# akim_sensorleri.net
KiCad netlist of a schematic drawn in EAGLE
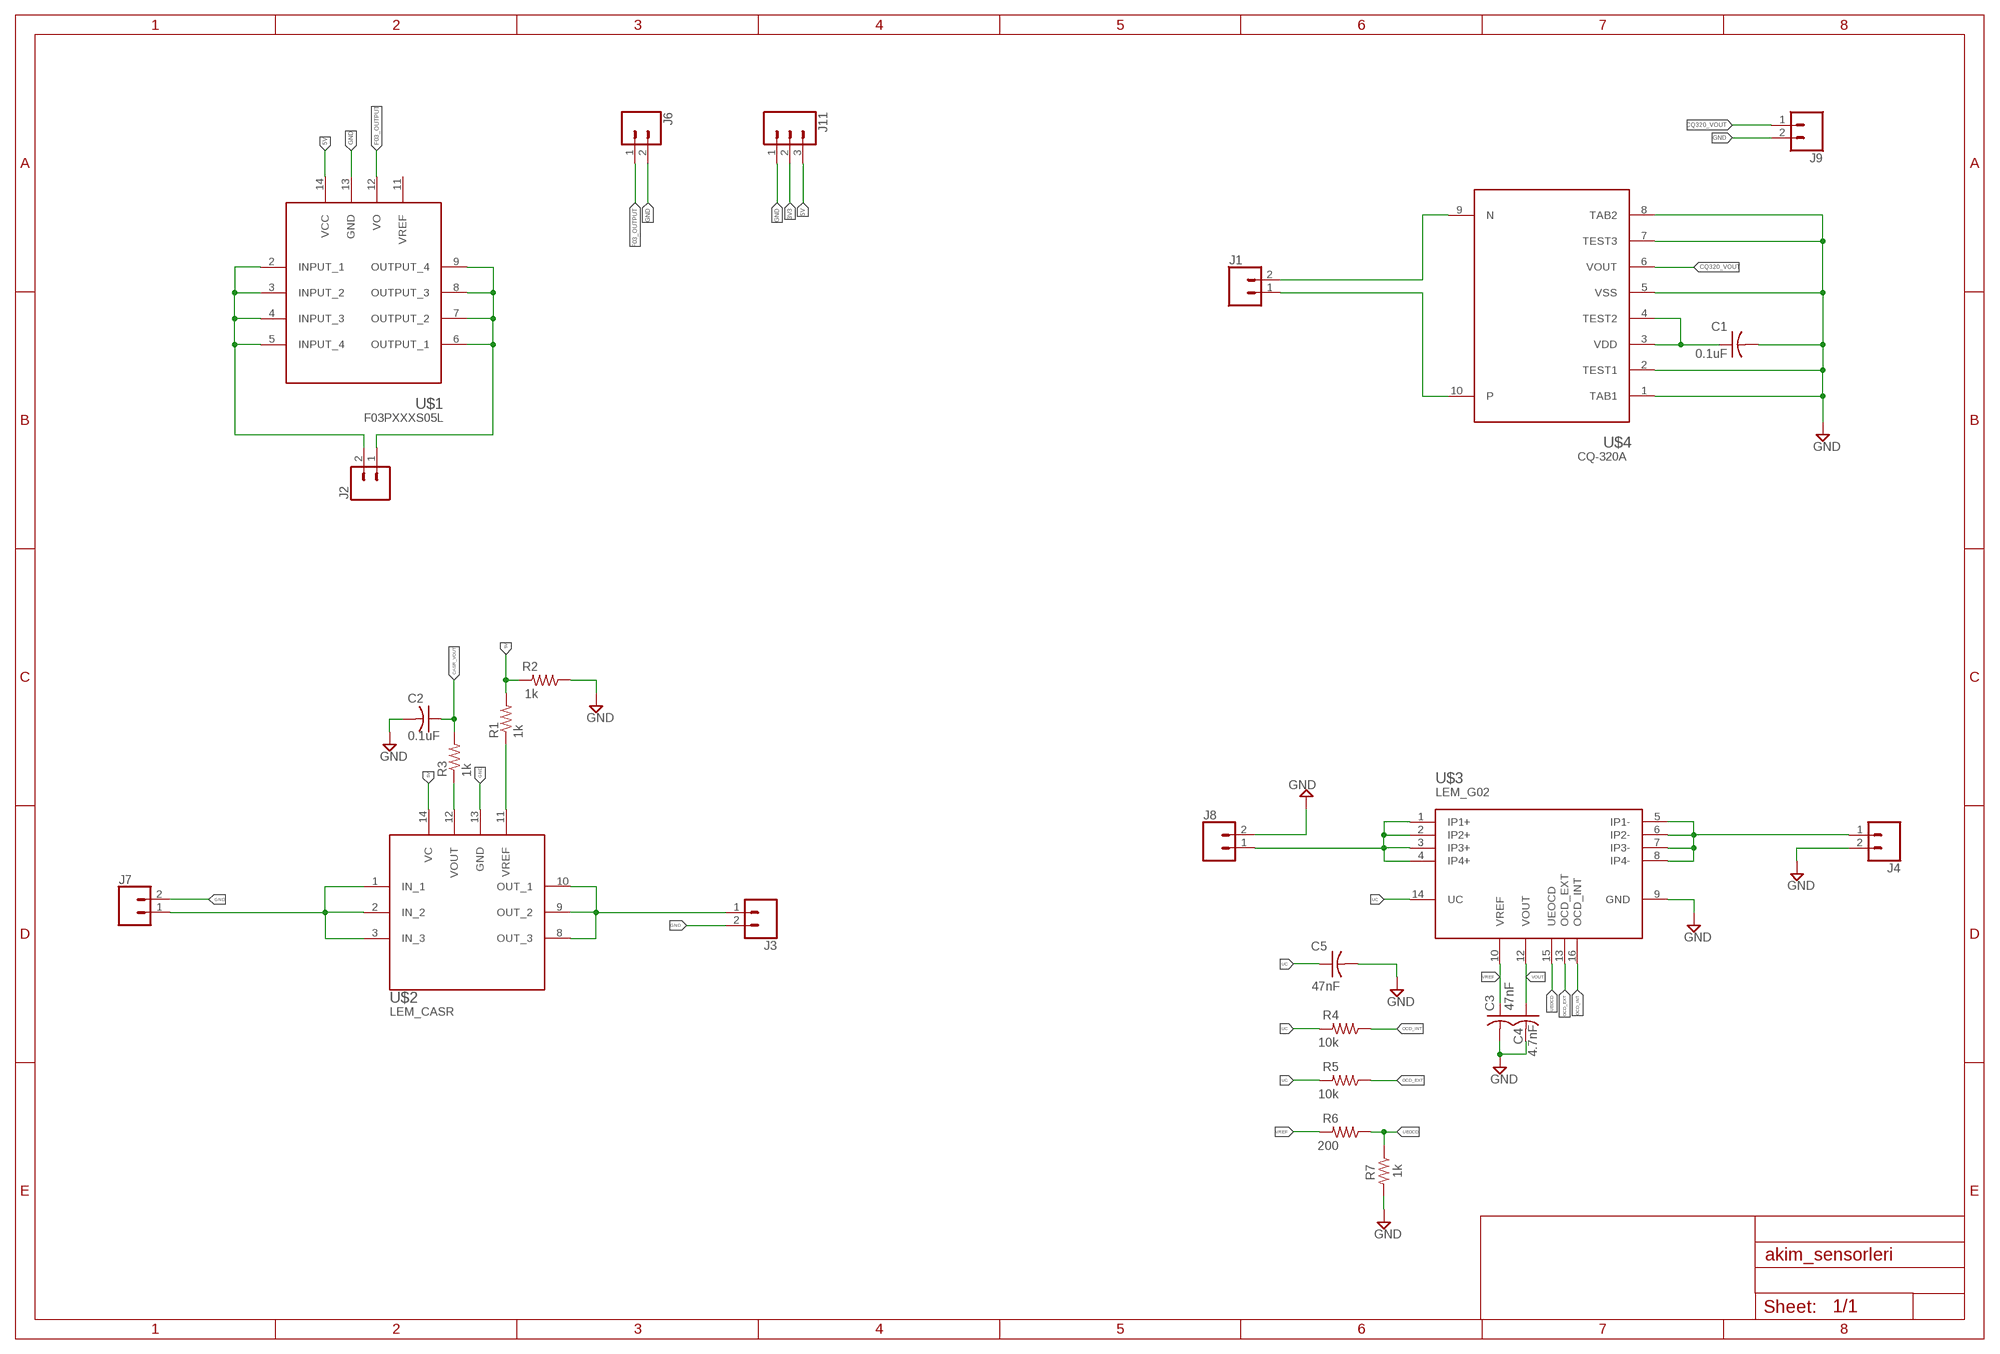
[diagram p0: schematic, sheet 1]

(export (version "E")
  (design (tool "Eeschema 10.0.6"))
  (components
    (comp (ref "C1")
      (value "0.1uF")
      (footprint "eagle-import:C1206")
      (libsource (lib "eagle-import") (part "C-USC1206"))
    )
    (comp (ref "C2")
      (value "0.1uF")
      (footprint "eagle-import:C1206")
      (libsource (lib "eagle-import") (part "C-USC1206"))
    )
    (comp (ref "C3")
      (value "47nF")
      (footprint "eagle-import:C1206")
      (libsource (lib "eagle-import") (part "C-USC1206"))
    )
    (comp (ref "C4")
      (value "4.7nF")
      (footprint "eagle-import:C1206")
      (libsource (lib "eagle-import") (part "C-USC1206"))
    )
    (comp (ref "C5")
      (value "47nF")
      (footprint "eagle-import:C1206")
      (libsource (lib "eagle-import") (part "C-USC1206"))
    )
    (comp (ref "J1")
      (value "CONN_025MM")
      (footprint "eagle-import:SCREWTERMINAL-5MM-2")
      (libsource (lib "eagle-import") (part "CONN_025MM"))
    )
    (comp (ref "J2")
      (value "CONN_025MM")
      (footprint "eagle-import:SCREWTERMINAL-5MM-2")
      (libsource (lib "eagle-import") (part "CONN_025MM"))
    )
    (comp (ref "J3")
      (value "CONN_025MM")
      (footprint "eagle-import:SCREWTERMINAL-5MM-2")
      (libsource (lib "eagle-import") (part "CONN_025MM"))
    )
    (comp (ref "J4")
      (value "CONN_025MM")
      (footprint "eagle-import:SCREWTERMINAL-5MM-2")
      (libsource (lib "eagle-import") (part "CONN_025MM"))
    )
    (comp (ref "J6")
      (value "CONN_025MM")
      (footprint "eagle-import:SCREWTERMINAL-5MM-2")
      (libsource (lib "eagle-import") (part "CONN_025MM"))
    )
    (comp (ref "J7")
      (value "CONN_025MM")
      (footprint "eagle-import:SCREWTERMINAL-5MM-2")
      (libsource (lib "eagle-import") (part "CONN_025MM"))
    )
    (comp (ref "J8")
      (value "CONN_025MM")
      (footprint "eagle-import:SCREWTERMINAL-5MM-2")
      (libsource (lib "eagle-import") (part "CONN_025MM"))
    )
    (comp (ref "J9")
      (value "CONN_025MM")
      (footprint "eagle-import:SCREWTERMINAL-5MM-2")
      (libsource (lib "eagle-import") (part "CONN_025MM"))
    )
    (comp (ref "J11")
      (value "CONN_03-SCREW-5MM")
      (footprint "eagle-import:SCREWTERMINAL-5MM-3")
      (libsource (lib "eagle-import") (part "CONN_03-SCREW-5MM"))
    )
    (comp (ref "R1")
      (value "1k")
      (footprint "eagle-import:M1206")
      (libsource (lib "eagle-import") (part "R-US_M1206"))
    )
    (comp (ref "R2")
      (value "1k")
      (footprint "eagle-import:M1206")
      (libsource (lib "eagle-import") (part "R-US_M1206"))
    )
    (comp (ref "R3")
      (value "1k")
      (footprint "eagle-import:M1206")
      (libsource (lib "eagle-import") (part "R-US_M1206"))
    )
    (comp (ref "R4")
      (value "10k")
      (footprint "eagle-import:M1206")
      (libsource (lib "eagle-import") (part "R-US_M1206"))
    )
    (comp (ref "R5")
      (value "10k")
      (footprint "eagle-import:M1206")
      (libsource (lib "eagle-import") (part "R-US_M1206"))
    )
    (comp (ref "R6")
      (value "200")
      (footprint "eagle-import:M1206")
      (libsource (lib "eagle-import") (part "R-US_M1206"))
    )
    (comp (ref "R7")
      (value "1k")
      (footprint "eagle-import:M1206")
      (libsource (lib "eagle-import") (part "R-US_M1206"))
    )
    (comp (ref "U$1")
      (value "F03PXXXS05L")
      (footprint "eagle-import:F03PXXXS05L")
      (libsource (lib "eagle-import") (part "F03PXXXS05L"))
    )
    (comp (ref "U$2")
      (value "LEM_CASR")
      (footprint "eagle-import:LEM")
      (libsource (lib "eagle-import") (part "LEM_CASR"))
    )
    (comp (ref "U$3")
      (value "LEM_G02")
      (footprint "eagle-import:LEM_G02")
      (libsource (lib "eagle-import") (part "LEM_G02"))
    )
    (comp (ref "U$4")
      (value "CQ-320A")
      (footprint "eagle-import:CQ-320A")
      (libsource (lib "eagle-import") (part "CQ-320A"))
    )
  )
  (nets
    (net (code "1") (name "3V3") (class "Default")
      (node (ref "J11") (pin "2") (pinfunction "2_2") (pintype "passive"))
    )
    (net (code "2") (name "5V") (class "Default")
      (node (ref "J11") (pin "3") (pinfunction "3_3") (pintype "passive"))
      (node (ref "R1") (pin "2") (pinfunction "2_2") (pintype "passive"))
      (node (ref "R2") (pin "2") (pinfunction "2_2") (pintype "passive"))
      (node (ref "U$1") (pin "14") (pinfunction "VCC_14") (pintype "bidirectional"))
      (node (ref "U$2") (pin "14") (pinfunction "VC_14") (pintype "bidirectional"))
    )
    (net (code "3") (name "CASR_VOUT") (class "Default")
      (node (ref "C2") (pin "1") (pinfunction "1_1") (pintype "passive"))
      (node (ref "R3") (pin "2") (pinfunction "2_2") (pintype "passive"))
    )
    (net (code "4") (name "CQ320_VOUT") (class "Default")
      (node (ref "J9") (pin "1") (pinfunction "1_1") (pintype "passive"))
      (node (ref "U$4") (pin "6") (pinfunction "VOUT_6") (pintype "bidirectional"))
    )
    (net (code "5") (name "F03_OUTPUT") (class "Default")
      (node (ref "J6") (pin "1") (pinfunction "1_1") (pintype "passive"))
      (node (ref "U$1") (pin "12") (pinfunction "VO_12") (pintype "bidirectional"))
    )
    (net (code "6") (name "GND") (class "Default")
      (node (ref "C1") (pin "2") (pinfunction "2_2") (pintype "passive"))
      (node (ref "C2") (pin "2") (pinfunction "2_2") (pintype "passive"))
      (node (ref "C3") (pin "2") (pinfunction "2_2") (pintype "passive"))
      (node (ref "C4") (pin "2") (pinfunction "2_2") (pintype "passive"))
      (node (ref "C5") (pin "2") (pinfunction "2_2") (pintype "passive"))
      (node (ref "J11") (pin "1") (pinfunction "1_1") (pintype "passive"))
      (node (ref "J3") (pin "2") (pinfunction "2_2") (pintype "passive"))
      (node (ref "J4") (pin "2") (pinfunction "2_2") (pintype "passive"))
      (node (ref "J6") (pin "2") (pinfunction "2_2") (pintype "passive"))
      (node (ref "J7") (pin "2") (pinfunction "2_2") (pintype "passive"))
      (node (ref "J8") (pin "2") (pinfunction "2_2") (pintype "passive"))
      (node (ref "J9") (pin "2") (pinfunction "2_2") (pintype "passive"))
      (node (ref "R2") (pin "1") (pinfunction "1_1") (pintype "passive"))
      (node (ref "R7") (pin "2") (pinfunction "2_2") (pintype "passive"))
      (node (ref "U$1") (pin "13") (pinfunction "GND_13") (pintype "bidirectional"))
      (node (ref "U$2") (pin "13") (pinfunction "GND_13") (pintype "bidirectional"))
      (node (ref "U$3") (pin "9") (pinfunction "GND_9") (pintype "bidirectional"))
      (node (ref "U$4") (pin "1") (pinfunction "TAB1_1") (pintype "bidirectional"))
      (node (ref "U$4") (pin "2") (pinfunction "TEST1_2") (pintype "bidirectional"))
      (node (ref "U$4") (pin "5") (pinfunction "VSS_5") (pintype "bidirectional"))
      (node (ref "U$4") (pin "7") (pinfunction "TEST3_7") (pintype "bidirectional"))
      (node (ref "U$4") (pin "8") (pinfunction "TAB2_8") (pintype "bidirectional"))
    )
    (net (code "7") (name "Net-(U$1-INPUT_1)") (class "Default")
      (node (ref "J2") (pin "2") (pinfunction "2_2") (pintype "passive"))
      (node (ref "U$1") (pin "2") (pinfunction "INPUT_1_2") (pintype "bidirectional"))
      (node (ref "U$1") (pin "3") (pinfunction "INPUT_2_3") (pintype "bidirectional"))
      (node (ref "U$1") (pin "4") (pinfunction "INPUT_3_4") (pintype "bidirectional"))
      (node (ref "U$1") (pin "5") (pinfunction "INPUT_4_5") (pintype "bidirectional"))
    )
    (net (code "8") (name "Net-(U$1-OUTPUT_1)") (class "Default")
      (node (ref "J2") (pin "1") (pinfunction "1_1") (pintype "passive"))
      (node (ref "U$1") (pin "6") (pinfunction "OUTPUT_1_6") (pintype "bidirectional"))
      (node (ref "U$1") (pin "7") (pinfunction "OUTPUT_2_7") (pintype "bidirectional"))
      (node (ref "U$1") (pin "8") (pinfunction "OUTPUT_3_8") (pintype "bidirectional"))
      (node (ref "U$1") (pin "9") (pinfunction "OUTPUT_4_9") (pintype "bidirectional"))
    )
    (net (code "9") (name "Net-(U$2-IN_1)") (class "Default")
      (node (ref "J7") (pin "1") (pinfunction "1_1") (pintype "passive"))
      (node (ref "U$2") (pin "1") (pinfunction "IN_1_1") (pintype "bidirectional"))
      (node (ref "U$2") (pin "2") (pinfunction "IN_2_2") (pintype "bidirectional"))
      (node (ref "U$2") (pin "3") (pinfunction "IN_3_3") (pintype "bidirectional"))
    )
    (net (code "10") (name "Net-(U$2-OUT_1)") (class "Default")
      (node (ref "J3") (pin "1") (pinfunction "1_1") (pintype "passive"))
      (node (ref "U$2") (pin "10") (pinfunction "OUT_1_10") (pintype "bidirectional"))
      (node (ref "U$2") (pin "8") (pinfunction "OUT_3_8") (pintype "bidirectional"))
      (node (ref "U$2") (pin "9") (pinfunction "OUT_2_9") (pintype "bidirectional"))
    )
    (net (code "11") (name "Net-(U$2-VOUT)") (class "Default")
      (node (ref "R3") (pin "1") (pinfunction "1_1") (pintype "passive"))
      (node (ref "U$2") (pin "12") (pinfunction "VOUT_12") (pintype "bidirectional"))
    )
    (net (code "12") (name "Net-(U$2-VREF)") (class "Default")
      (node (ref "R1") (pin "1") (pinfunction "1_1") (pintype "passive"))
      (node (ref "U$2") (pin "11") (pinfunction "VREF_11") (pintype "bidirectional"))
    )
    (net (code "13") (name "Net-(U$3-IP1+)") (class "Default")
      (node (ref "J8") (pin "1") (pinfunction "1_1") (pintype "passive"))
      (node (ref "U$3") (pin "1") (pinfunction "IP1+_1") (pintype "bidirectional"))
      (node (ref "U$3") (pin "2") (pinfunction "IP2+_2") (pintype "bidirectional"))
      (node (ref "U$3") (pin "3") (pinfunction "IP3+_3") (pintype "bidirectional"))
      (node (ref "U$3") (pin "4") (pinfunction "IP4+_4") (pintype "bidirectional"))
    )
    (net (code "14") (name "Net-(U$3-IP1-)") (class "Default")
      (node (ref "J4") (pin "1") (pinfunction "1_1") (pintype "passive"))
      (node (ref "U$3") (pin "5") (pinfunction "IP1-_5") (pintype "bidirectional"))
      (node (ref "U$3") (pin "6") (pinfunction "IP2-_6") (pintype "bidirectional"))
      (node (ref "U$3") (pin "7") (pinfunction "IP3-_7") (pintype "bidirectional"))
      (node (ref "U$3") (pin "8") (pinfunction "IP4-_8") (pintype "bidirectional"))
    )
    (net (code "15") (name "Net-(U$4-N)") (class "Default")
      (node (ref "J1") (pin "2") (pinfunction "2_2") (pintype "passive"))
      (node (ref "U$4") (pin "9") (pinfunction "N_9") (pintype "bidirectional"))
    )
    (net (code "16") (name "Net-(U$4-P)") (class "Default")
      (node (ref "J1") (pin "1") (pinfunction "1_1") (pintype "passive"))
      (node (ref "U$4") (pin "10") (pinfunction "P_10") (pintype "bidirectional"))
    )
    (net (code "17") (name "Net-(U$4-TEST2)") (class "Default")
      (node (ref "C1") (pin "1") (pinfunction "1_1") (pintype "passive"))
      (node (ref "U$4") (pin "3") (pinfunction "VDD_3") (pintype "bidirectional"))
      (node (ref "U$4") (pin "4") (pinfunction "TEST2_4") (pintype "bidirectional"))
    )
    (net (code "18") (name "OCD_EXT") (class "Default")
      (node (ref "R5") (pin "1") (pinfunction "1_1") (pintype "passive"))
      (node (ref "U$3") (pin "13") (pinfunction "OCD_EXT_13") (pintype "bidirectional"))
    )
    (net (code "19") (name "OCD_INT") (class "Default")
      (node (ref "R4") (pin "1") (pinfunction "1_1") (pintype "passive"))
      (node (ref "U$3") (pin "16") (pinfunction "OCD_INT_16") (pintype "bidirectional"))
    )
    (net (code "20") (name "UC") (class "Default")
      (node (ref "C5") (pin "1") (pinfunction "1_1") (pintype "passive"))
      (node (ref "R4") (pin "2") (pinfunction "2_2") (pintype "passive"))
      (node (ref "R5") (pin "2") (pinfunction "2_2") (pintype "passive"))
      (node (ref "U$3") (pin "14") (pinfunction "UC_14") (pintype "bidirectional"))
    )
    (net (code "21") (name "UEOCD") (class "Default")
      (node (ref "R6") (pin "1") (pinfunction "1_1") (pintype "passive"))
      (node (ref "R7") (pin "1") (pinfunction "1_1") (pintype "passive"))
      (node (ref "U$3") (pin "15") (pinfunction "UEOCD_15") (pintype "bidirectional"))
    )
    (net (code "22") (name "VOUT") (class "Default")
      (node (ref "C4") (pin "1") (pinfunction "1_1") (pintype "passive"))
      (node (ref "U$3") (pin "12") (pinfunction "VOUT_12") (pintype "bidirectional"))
    )
    (net (code "23") (name "VREF") (class "Default")
      (node (ref "C3") (pin "1") (pinfunction "1_1") (pintype "passive"))
      (node (ref "R6") (pin "2") (pinfunction "2_2") (pintype "passive"))
      (node (ref "U$3") (pin "10") (pinfunction "VREF_10") (pintype "bidirectional"))
    )
    (net (code "24") (name "unconnected-(U$1-VREF-Pad11)") (class "Default")
      (node (ref "U$1") (pin "11") (pinfunction "VREF_11") (pintype "bidirectional"))
    )
  )
)
